# R_gulateur_USB_HT_BT.net
KiCad netlist of a schematic drawn in Altium Designer
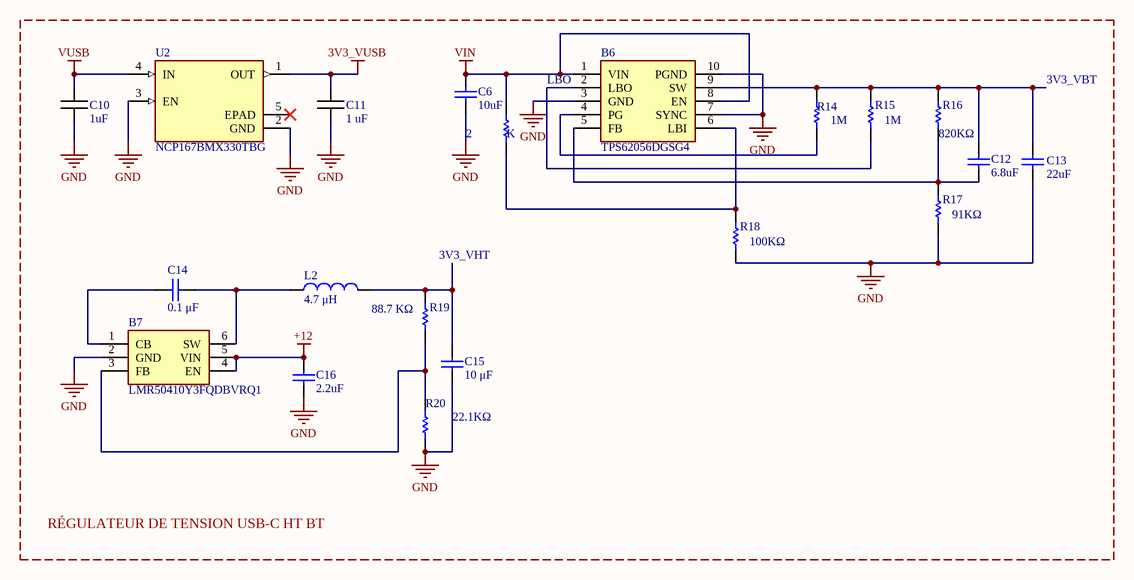
[diagram p0: Régulateur USB HT BT.SchDoc]

(export (version "E")
  (design (tool "Eeschema 10.0.6"))
  (components
    (comp (ref "2")
      (value "K")
      (description "Resistor")
      (fields (field (name "Comment") "R6"))
      (libsource (lib "") (part "Resistor_1"))
    )
    (comp (ref "B6")
      (value "TPS62056DGSG4")
      (footprint "SOP50P490X110-10N")
      (fields (field (name "MOUSER PART NUMBER") "595-TPS62056DGSG4"))
      (libsource (lib "SCHLibrary") (part "TPS62056DGSG4"))
    )
    (comp (ref "B7")
      (value "LMR50410Y3FQDBVRQ1")
      (footprint "SOT95P280X145-6N")
      (fields (field (name "MOUSER PART NUMBER") "595-R50410Y3FQDBVRQ1"))
      (libsource (lib "SCHLibrary") (part "LMR50410Y3FQDBVRQ1"))
    )
    (comp (ref "C6")
      (value "10uF")
      (description "Capacitor")
      (fields (field (name "Comment") "Comment"))
      (libsource (lib "") (part "Capacitor_1"))
    )
    (comp (ref "C10")
      (value "1uF")
      (footprint "CAPC1005X06N")
      (libsource (lib "SCHLibrary") (part "Capacitor"))
    )
    (comp (ref "C11")
      (value "1 uF")
      (footprint "CAPC1005X06N")
      (libsource (lib "SCHLibrary") (part "Capacitor"))
    )
    (comp (ref "C12")
      (value "6.8uF")
      (description "Capacitor")
      (fields (field (name "Comment") "Comment"))
      (libsource (lib "") (part "Capacitor_2"))
    )
    (comp (ref "C13")
      (value "22uF")
      (description "Capacitor")
      (fields (field (name "Comment") "Comment"))
      (libsource (lib "") (part "Capacitor_2"))
    )
    (comp (ref "C14")
      (value "0.1 μF")
      (description "Capacitor")
      (fields (field (name "Comment") "Comment"))
      (libsource (lib "Simulation Generic Components") (part "Capacitor"))
    )
    (comp (ref "C15")
      (value "10 μF")
      (description "Capacitor")
      (fields (field (name "Comment") "Comment"))
      (libsource (lib "") (part "Capacitor_2"))
    )
    (comp (ref "C16")
      (value "2.2uF")
      (description "Capacitor")
      (fields (field (name "Comment") "Comment"))
      (libsource (lib "") (part "Capacitor_1"))
    )
    (comp (ref "L2")
      (value "4.7 μH")
      (description "Inductor")
      (fields (field (name "Comment") "Comment"))
      (libsource (lib "Simulation Generic Components") (part "Inductor"))
    )
    (comp (ref "R14")
      (value "1M")
      (description "Resistor")
      (fields (field (name "Comment") "Comment"))
      (libsource (lib "") (part "Resistor_2"))
    )
    (comp (ref "R15")
      (value "1M")
      (description "Resistor")
      (fields (field (name "Comment") "Comment"))
      (libsource (lib "") (part "Resistor_2"))
    )
    (comp (ref "R16")
      (value "820KΩ")
      (description "Resistor")
      (fields (field (name "Comment") "Comment"))
      (libsource (lib "") (part "Resistor_2"))
    )
    (comp (ref "R17")
      (value "91KΩ")
      (description "Resistor")
      (fields (field (name "Comment") "Comment"))
      (libsource (lib "") (part "Resistor_1"))
    )
    (comp (ref "R18")
      (value "100KΩ")
      (description "Resistor")
      (fields (field (name "Comment") "Comment"))
      (libsource (lib "Simulation Generic Components") (part "Resistor"))
    )
    (comp (ref "R19")
      (value "88.7 KΩ")
      (description "Resistor")
      (fields (field (name "Comment") "Comment"))
      (libsource (lib "") (part "Resistor_2"))
    )
    (comp (ref "R20")
      (value "22.1KΩ")
      (description "Resistor")
      (fields (field (name "Comment") "Comment"))
      (libsource (lib "Simulation Generic Components") (part "Resistor"))
    )
    (comp (ref "U2")
      (value "NCP167BMX330TBG")
      (footprint "NCP167BMX330TBG")
      (description "Régulateurs de tension LDO LDO 700 MA ULTRA-LOW NOISE 3.3V")
      (libsource (lib "SCHLibrary") (part "NCP167BMX330TBG"))
    )
  )
  (nets
    (net (code "1") (name "+12") (class "Default")
      (node (ref "B7") (pin "4") (pinfunction "EN_4") (pintype "passive"))
      (node (ref "B7") (pin "5") (pinfunction "VIN_5") (pintype "passive"))
      (node (ref "C16") (pin "1") (pinfunction "1_1") (pintype "passive"))
    )
    (net (code "2") (name "3V3_VUSB") (class "Default")
      (node (ref "C11") (pin "2") (pinfunction "2_2") (pintype "passive"))
      (node (ref "U2") (pin "1") (pinfunction "OUT_1") (pintype "output"))
    )
    (net (code "3") (name "GND") (class "Default")
      (node (ref "B6") (pin "10") (pinfunction "PGND_10") (pintype "passive"))
      (node (ref "B6") (pin "3") (pinfunction "GND_3") (pintype "passive"))
      (node (ref "B6") (pin "7") (pinfunction "SYNC_7") (pintype "passive"))
      (node (ref "B7") (pin "2") (pinfunction "GND_2") (pintype "passive"))
      (node (ref "C10") (pin "1") (pinfunction "1_1") (pintype "passive"))
      (node (ref "C11") (pin "1") (pinfunction "1_1") (pintype "passive"))
      (node (ref "C13") (pin "2") (pinfunction "2_2") (pintype "passive"))
      (node (ref "C15") (pin "2") (pinfunction "2_2") (pintype "passive"))
      (node (ref "C16") (pin "2") (pinfunction "2_2") (pintype "passive"))
      (node (ref "C6") (pin "2") (pinfunction "2_2") (pintype "passive"))
      (node (ref "R17") (pin "1") (pinfunction "1_1") (pintype "passive"))
      (node (ref "R18") (pin "2") (pinfunction "2_2") (pintype "passive"))
      (node (ref "R20") (pin "2") (pinfunction "2_2") (pintype "passive"))
      (node (ref "U2") (pin "2") (pinfunction "GND_2") (pintype "power_in"))
      (node (ref "U2") (pin "3") (pinfunction "EN_3") (pintype "input"))
    )
    (net (code "4") (name "Net-(B6-FB)") (class "Default")
      (node (ref "B6") (pin "5") (pinfunction "FB_5") (pintype "passive"))
      (node (ref "C12") (pin "2") (pinfunction "2_2") (pintype "passive"))
      (node (ref "R16") (pin "2") (pinfunction "2_2") (pintype "passive"))
      (node (ref "R17") (pin "2") (pinfunction "2_2") (pintype "passive"))
    )
    (net (code "5") (name "Net-(B6-LBI)") (class "Default")
      (node (ref "2") (pin "1") (pinfunction "1_1") (pintype "passive"))
      (node (ref "B6") (pin "6") (pinfunction "LBI_6") (pintype "passive"))
      (node (ref "R18") (pin "1") (pinfunction "1_1") (pintype "passive"))
    )
    (net (code "6") (name "Net-(B6-LBO)") (class "Default")
      (node (ref "B6") (pin "2") (pinfunction "LBO_2") (pintype "passive"))
      (node (ref "R15") (pin "2") (pinfunction "2_2") (pintype "passive"))
    )
    (net (code "7") (name "Net-(B6-PG)") (class "Default")
      (node (ref "B6") (pin "4") (pinfunction "PG_4") (pintype "passive"))
      (node (ref "R14") (pin "2") (pinfunction "2_2") (pintype "passive"))
    )
    (net (code "8") (name "Net-(B6-SW)") (class "Default")
      (node (ref "B6") (pin "9") (pinfunction "SW_9") (pintype "passive"))
      (node (ref "C12") (pin "2") (pinfunction "2_2") (pintype "passive"))
      (node (ref "C13") (pin "2") (pinfunction "2_2") (pintype "passive"))
      (node (ref "R14") (pin "2") (pinfunction "2_2") (pintype "passive"))
      (node (ref "R15") (pin "2") (pinfunction "2_2") (pintype "passive"))
      (node (ref "R16") (pin "2") (pinfunction "2_2") (pintype "passive"))
    )
    (net (code "9") (name "Net-(B7-CB)") (class "Default")
      (node (ref "B7") (pin "1") (pinfunction "CB_1") (pintype "passive"))
      (node (ref "C14") (pin "1") (pinfunction "1_1") (pintype "passive"))
    )
    (net (code "10") (name "Net-(B7-FB)") (class "Default")
      (node (ref "B7") (pin "3") (pinfunction "FB_3") (pintype "passive"))
      (node (ref "R19") (pin "2") (pinfunction "2_2") (pintype "passive"))
      (node (ref "R20") (pin "1") (pinfunction "1_1") (pintype "passive"))
    )
    (net (code "11") (name "Net-(B7-SW)") (class "Default")
      (node (ref "B7") (pin "6") (pinfunction "SW_6") (pintype "passive"))
      (node (ref "C14") (pin "2") (pinfunction "2_2") (pintype "passive"))
      (node (ref "L2") (pin "1") (pinfunction "1_1") (pintype "passive"))
    )
    (net (code "12") (name "Net-(C15-Pad2)") (class "Default")
      (node (ref "C15") (pin "2") (pinfunction "2_2") (pintype "passive"))
      (node (ref "L2") (pin "2") (pinfunction "2_2") (pintype "passive"))
      (node (ref "R19") (pin "2") (pinfunction "2_2") (pintype "passive"))
    )
    (net (code "13") (name "VIN") (class "Default")
      (node (ref "2") (pin "2") (pinfunction "2_2") (pintype "passive"))
      (node (ref "B6") (pin "1") (pinfunction "VIN_1") (pintype "passive"))
      (node (ref "B6") (pin "8") (pinfunction "EN_8") (pintype "passive"))
      (node (ref "C6") (pin "1") (pinfunction "1_1") (pintype "passive"))
    )
    (net (code "14") (name "VUSB") (class "Default")
      (node (ref "C10") (pin "2") (pinfunction "2_2") (pintype "passive"))
      (node (ref "U2") (pin "4") (pinfunction "IN_4") (pintype "input"))
    )
    (net (code "15") (name "unconnected-(U2-EPAD-Pad5)") (class "Default")
      (node (ref "U2") (pin "5") (pinfunction "EPAD_5") (pintype "power_in+no_connect"))
    )
  )
)
